# MJ808_clone_-_all_driver-_POC.net
KiCad netlist of a schematic drawn in EAGLE
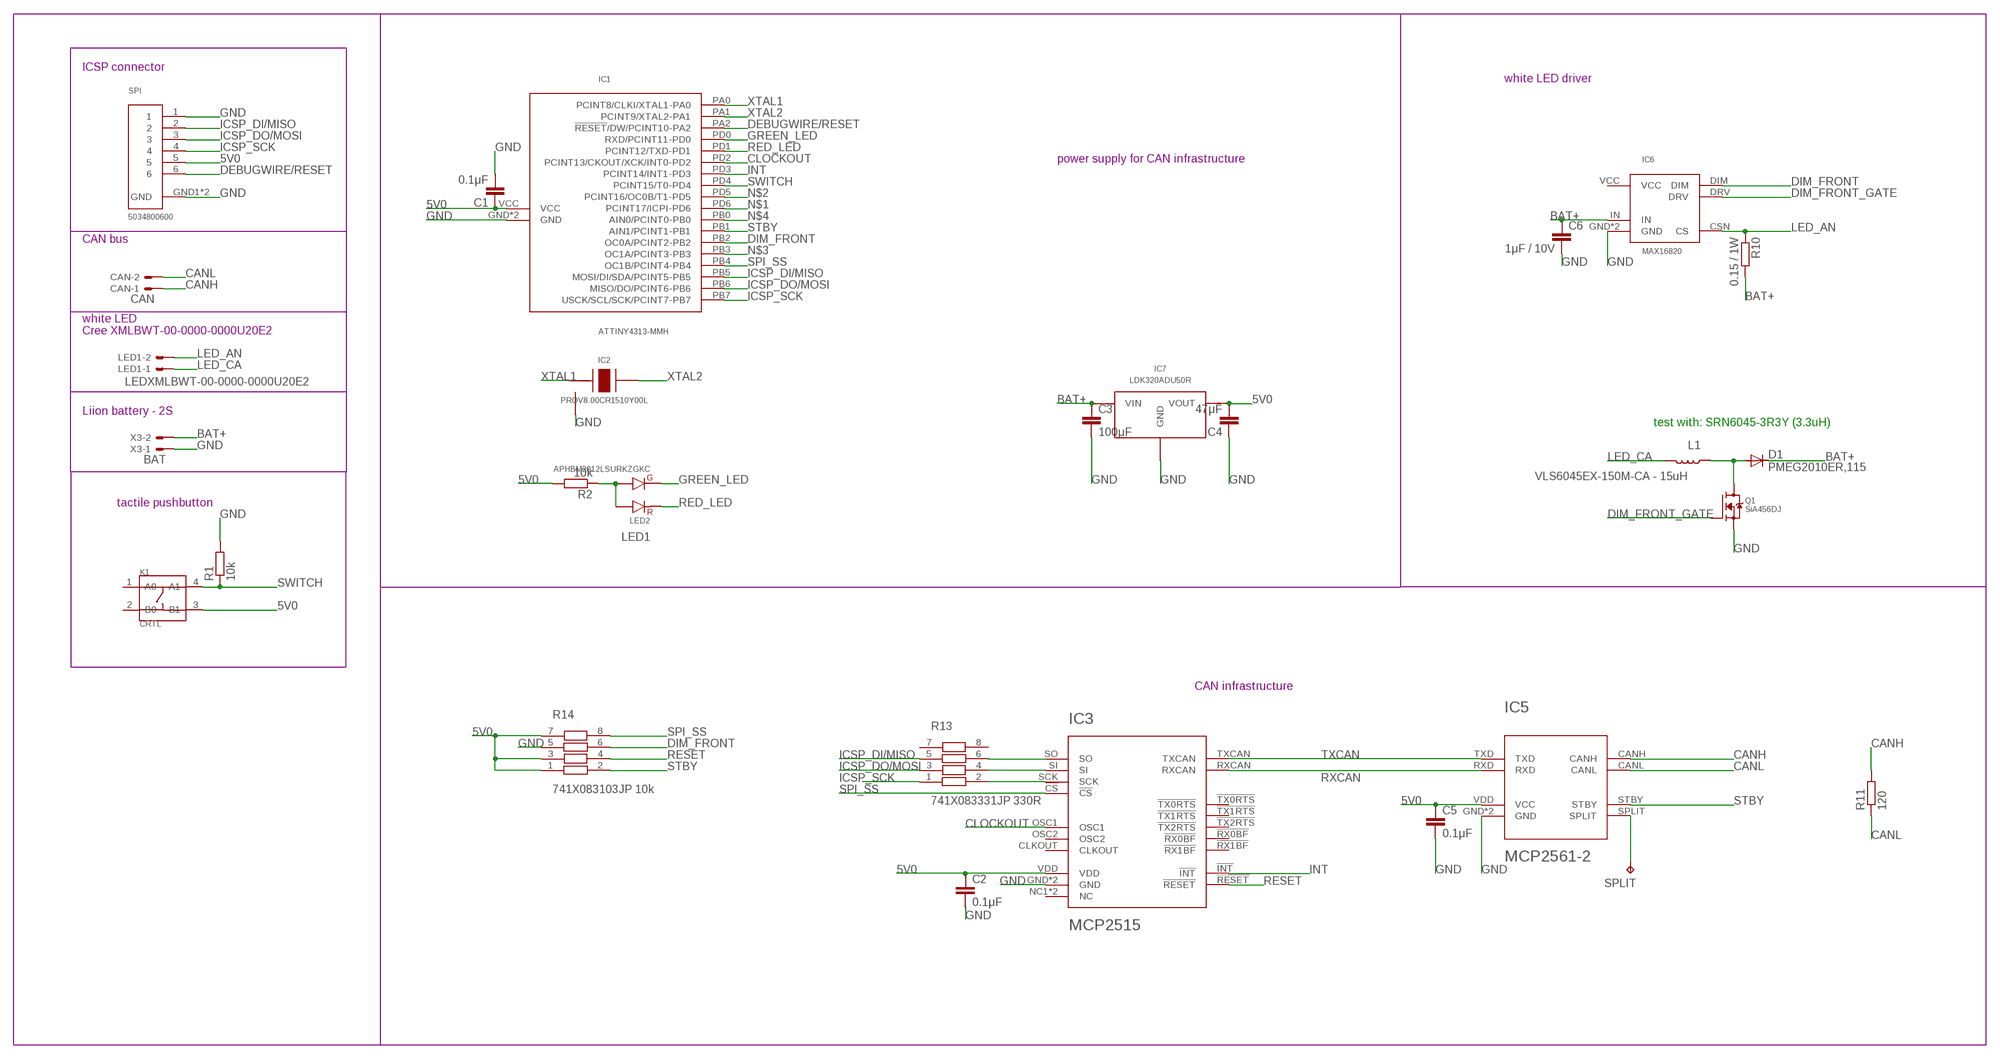
[diagram p0: schematic, sheet 1]

(export (version "E")
  (design (tool "Eeschema 10.0.6"))
  (components
    (comp (ref "C1")
      (value "0.1μF")
      (footprint "eagle-import:C0402")
      (libsource (lib "eagle-import") (part "C-EUC0402"))
    )
    (comp (ref "C2")
      (value "0.1μF")
      (footprint "eagle-import:C0402")
      (libsource (lib "eagle-import") (part "C-EUC0402"))
    )
    (comp (ref "C3")
      (value "100μF")
      (footprint "eagle-import:C1206")
      (libsource (lib "eagle-import") (part "C-EUC1206"))
    )
    (comp (ref "C4")
      (value "47μF")
      (footprint "eagle-import:C0805")
      (libsource (lib "eagle-import") (part "C-EUC0805"))
    )
    (comp (ref "C5")
      (value "0.1μF")
      (footprint "eagle-import:C0402")
      (libsource (lib "eagle-import") (part "C-EUC0402"))
    )
    (comp (ref "C6")
      (value "1μF / 10V")
      (footprint "eagle-import:C0805")
      (libsource (lib "eagle-import") (part "C-EUC0805"))
    )
    (comp (ref "CAN")
      (value "CAN")
      (footprint "eagle-import:22-23-2021")
      (fields (field (name "MF") "MOLEX") (field (name "MPN") "22-23-2021"))
      (libsource (lib "eagle-import") (part "22-23-2021"))
    )
    (comp (ref "D1")
      (value "PMEG2010ER,115")
      (footprint "eagle-import:SOD123")
      (libsource (lib "eagle-import") (part "DIODE-SOD123"))
    )
    (comp (ref "IC1")
      (value "ATTINY4313-MMH")
      (footprint "eagle-import:VQFN-20")
      (fields (field (name "SPICEPREFIX") "X"))
      (libsource (lib "eagle-import") (part "ATTINY4313VQFN-20"))
    )
    (comp (ref "IC2")
      (value "PRQV8.00CR1510Y00L")
      (footprint "eagle-import:SMT")
      (libsource (lib "eagle-import") (part "PRQV"))
    )
    (comp (ref "IC3")
      (value "MCP2515")
      (footprint "eagle-import:QFN20")
      (libsource (lib "eagle-import") (part "MCP2515-I-ML"))
    )
    (comp (ref "IC5")
      (value "MCP2561-2")
      (footprint "eagle-import:DFN10")
      (libsource (lib "eagle-import") (part "MCP2561-2"))
    )
    (comp (ref "IC6")
      (value "MAX16820")
      (footprint "eagle-import:TDFN-6-EP")
      (libsource (lib "eagle-import") (part "MAX16820"))
    )
    (comp (ref "IC7")
      (value "LDK320ADU50R")
      (footprint "eagle-import:SOT-89")
      (libsource (lib "eagle-import") (part "LDO"))
    )
    (comp (ref "K1")
      (value "CRTL")
      (footprint "eagle-import:SW4-SMD-6.0X6.0X5.0MM")
      (fields (field (name "MPN") "DTSM-62K-S-V-T/R(SN431)"))
      (libsource (lib "eagle-import") (part "SMD-SWITCH-TACTILE-SPST-NO(4P-D6.0MM)"))
    )
    (comp (ref "L1")
      (value "VLS6045EX-150M-CA - 15uH")
      (footprint "eagle-import:SRN6045")
      (libsource (lib "eagle-import") (part "INDUCTOR-SRN6045-33UH"))
    )
    (comp (ref "LED1")
      (value "LEDXMLBWT-00-0000-0000U20E2")
      (footprint "eagle-import:22-23-2021")
      (fields (field (name "MF") "MOLEX") (field (name "MPN") "22-23-2021"))
      (libsource (lib "eagle-import") (part "22-23-2021"))
    )
    (comp (ref "LED2")
      (value "APHBM2012LSURKZGKC")
      (footprint "eagle-import:SMD")
      (libsource (lib "eagle-import") (part "APHBM2012LSURKZGKC"))
    )
    (comp (ref "Q1")
      (value "SiA456DJ")
      (footprint "eagle-import:SC-70-6")
      (libsource (lib "eagle-import") (part "SIA456DJ"))
    )
    (comp (ref "R1")
      (value "10k")
      (footprint "eagle-import:R0402")
      (libsource (lib "eagle-import") (part "R-EU_R0402"))
    )
    (comp (ref "R2")
      (value "10k")
      (footprint "eagle-import:R0402")
      (libsource (lib "eagle-import") (part "R-EU_R0402"))
    )
    (comp (ref "R10")
      (value "0.15 / 1W")
      (footprint "eagle-import:R1210")
      (libsource (lib "eagle-import") (part "R-EU_R1210"))
    )
    (comp (ref "R11")
      (value "120")
      (footprint "eagle-import:R0805")
      (libsource (lib "eagle-import") (part "R-EU_R0805"))
    )
    (comp (ref "R13")
      (value "741X083331JP 330R")
      (footprint "eagle-import:0402")
      (libsource (lib "eagle-import") (part "741X083331JP"))
    )
    (comp (ref "R14")
      (value "741X083103JP 10k")
      (footprint "eagle-import:0402")
      (libsource (lib "eagle-import") (part "741X083331JP"))
    )
    (comp (ref "SPI")
      (value "5034800600")
      (footprint "eagle-import:SMT")
      (libsource (lib "eagle-import") (part "5034800600"))
    )
    (comp (ref "SPLIT")
      (value "TPB2,54")
      (footprint "eagle-import:B2,54")
      (libsource (lib "eagle-import") (part "TPB2,54"))
    )
    (comp (ref "X3")
      (value "BAT")
      (footprint "eagle-import:22-23-2021")
      (fields (field (name "MF") "MOLEX") (field (name "MPN") "22-23-2021"))
      (libsource (lib "eagle-import") (part "22-23-2021"))
    )
  )
  (nets
    (net (code "1") (name "/5V0") (class "Default")
      (node (ref "C1") (pin "1") (pinfunction "1_1") (pintype "passive"))
      (node (ref "C2") (pin "1") (pinfunction "1_1") (pintype "passive"))
      (node (ref "C4") (pin "2") (pinfunction "2_2") (pintype "passive"))
      (node (ref "C5") (pin "1") (pinfunction "1_1") (pintype "passive"))
      (node (ref "IC1") (pin "VCC") (pinfunction "VCC_VCC") (pintype "bidirectional"))
      (node (ref "IC3") (pin "VDD") (pinfunction "VDD_VDD") (pintype "power_in"))
      (node (ref "IC5") (pin "VDD") (pinfunction "VCC_VDD") (pintype "power_in"))
      (node (ref "IC7") (pin "VOUT") (pinfunction "VOUT_VOUT") (pintype "bidirectional"))
      (node (ref "K1") (pin "3") (pinfunction "B1_3") (pintype "bidirectional"))
      (node (ref "R14") (pin "1") (pinfunction "1_1") (pintype "bidirectional"))
      (node (ref "R14") (pin "3") (pinfunction "3_3") (pintype "bidirectional"))
      (node (ref "R14") (pin "7") (pinfunction "7_7") (pintype "bidirectional"))
      (node (ref "R2") (pin "2") (pinfunction "2_2") (pintype "passive"))
      (node (ref "SPI") (pin "5") (pinfunction "5_5") (pintype "bidirectional"))
    )
    (net (code "2") (name "/BAT+") (class "Default")
      (node (ref "C3") (pin "1") (pinfunction "1_1") (pintype "passive"))
      (node (ref "C6") (pin "1") (pinfunction "1_1") (pintype "passive"))
      (node (ref "D1") (pin "C") (pinfunction "C_C") (pintype "passive"))
      (node (ref "IC6") (pin "IN") (pinfunction "IN_IN") (pintype "power_in"))
      (node (ref "IC7") (pin "VIN") (pinfunction "VIN_VIN") (pintype "bidirectional"))
      (node (ref "R10") (pin "2") (pinfunction "2_2") (pintype "passive"))
      (node (ref "X3") (pin "2") (pinfunction "S_2") (pintype "passive"))
    )
    (net (code "3") (name "/CANH") (class "Default")
      (node (ref "CAN") (pin "1") (pinfunction "S_1") (pintype "passive"))
      (node (ref "IC5") (pin "CANH") (pinfunction "CANH_CANH") (pintype "bidirectional"))
      (node (ref "R11") (pin "2") (pinfunction "2_2") (pintype "passive"))
    )
    (net (code "4") (name "/CANL") (class "Default")
      (node (ref "CAN") (pin "2") (pinfunction "S_2") (pintype "passive"))
      (node (ref "IC5") (pin "CANL") (pinfunction "CANL_CANL") (pintype "bidirectional"))
      (node (ref "R11") (pin "1") (pinfunction "1_1") (pintype "passive"))
    )
    (net (code "5") (name "/CLOCKOUT") (class "Default")
      (node (ref "IC1") (pin "PD2") (pinfunction "PCINT13/CKOUT/XCK/INT0-PD2_PD2") (pintype "bidirectional"))
      (node (ref "IC3") (pin "OSC1") (pinfunction "OSC1_OSC1") (pintype "bidirectional"))
    )
    (net (code "6") (name "/DEBUGWIRE{slash}RESET") (class "Default")
      (node (ref "IC1") (pin "PA2") (pinfunction "~{RESET}/DW/PCINT10-PA2_PA2") (pintype "bidirectional"))
      (node (ref "SPI") (pin "6") (pinfunction "6_6") (pintype "bidirectional"))
    )
    (net (code "7") (name "/DIM_FRONT") (class "Default")
      (node (ref "IC1") (pin "PB2") (pinfunction "OC0A/PCINT2-PB2_PB2") (pintype "bidirectional"))
      (node (ref "IC6") (pin "DIM") (pinfunction "DIM_DIM") (pintype "bidirectional"))
      (node (ref "R14") (pin "6") (pinfunction "6_6") (pintype "bidirectional"))
    )
    (net (code "8") (name "/DIM_FRONT_GATE") (class "Default")
      (node (ref "IC6") (pin "DRV") (pinfunction "DRV_DRV") (pintype "bidirectional"))
      (node (ref "Q1") (pin "G") (pinfunction "G_G") (pintype "passive"))
    )
    (net (code "9") (name "/GND") (class "Default")
      (node (ref "C1") (pin "2") (pinfunction "2_2") (pintype "passive"))
      (node (ref "C2") (pin "2") (pinfunction "2_2") (pintype "passive"))
      (node (ref "C3") (pin "2") (pinfunction "2_2") (pintype "passive"))
      (node (ref "C4") (pin "1") (pinfunction "1_1") (pintype "passive"))
      (node (ref "C5") (pin "2") (pinfunction "2_2") (pintype "passive"))
      (node (ref "C6") (pin "2") (pinfunction "2_2") (pintype "passive"))
      (node (ref "IC1") (pin "GND") (pinfunction "GND_GND") (pintype "bidirectional"))
      (node (ref "IC1") (pin "GND1") (pinfunction "GND_GND1") (pintype "bidirectional"))
      (node (ref "IC2") (pin "GND") (pinfunction "GND_GND") (pintype "bidirectional"))
      (node (ref "IC3") (pin "GND") (pinfunction "GND_GND") (pintype "power_in"))
      (node (ref "IC3") (pin "GND6") (pinfunction "GND_GND6") (pintype "power_in"))
      (node (ref "IC5") (pin "GND") (pinfunction "GND_GND") (pintype "power_in"))
      (node (ref "IC5") (pin "VSS") (pinfunction "GND_VSS") (pintype "power_in"))
      (node (ref "IC6") (pin "GND") (pinfunction "GND_GND") (pintype "power_in"))
      (node (ref "IC6") (pin "GND1") (pinfunction "GND_GND1") (pintype "power_in"))
      (node (ref "IC7") (pin "GND") (pinfunction "GND_GND") (pintype "bidirectional"))
      (node (ref "Q1") (pin "S") (pinfunction "S_S") (pintype "passive"))
      (node (ref "R1") (pin "2") (pinfunction "2_2") (pintype "passive"))
      (node (ref "R14") (pin "5") (pinfunction "5_5") (pintype "bidirectional"))
      (node (ref "SPI") (pin "1") (pinfunction "1_1") (pintype "bidirectional"))
      (node (ref "SPI") (pin "GND1") (pinfunction "GND_GND1") (pintype "bidirectional"))
      (node (ref "SPI") (pin "GND2") (pinfunction "GND_GND2") (pintype "bidirectional"))
      (node (ref "X3") (pin "1") (pinfunction "S_1") (pintype "passive"))
    )
    (net (code "10") (name "/GREEN_LED") (class "Default")
      (node (ref "IC1") (pin "PD0") (pinfunction "RXD/PCINT11-PD0_PD0") (pintype "bidirectional"))
      (node (ref "LED2") (pin "3") (pinfunction "3_3") (pintype "bidirectional"))
    )
    (net (code "11") (name "/ICSP_DI{slash}MISO") (class "Default")
      (node (ref "IC1") (pin "PB5") (pinfunction "MOSI/DI/SDA/PCINT5-PB5_PB5") (pintype "bidirectional"))
      (node (ref "R13") (pin "5") (pinfunction "5_5") (pintype "bidirectional"))
      (node (ref "SPI") (pin "2") (pinfunction "2_2") (pintype "bidirectional"))
    )
    (net (code "12") (name "/ICSP_DO{slash}MOSI") (class "Default")
      (node (ref "IC1") (pin "PB6") (pinfunction "MISO/DO/PCINT6-PB6_PB6") (pintype "bidirectional"))
      (node (ref "R13") (pin "3") (pinfunction "3_3") (pintype "bidirectional"))
      (node (ref "SPI") (pin "3") (pinfunction "3_3") (pintype "bidirectional"))
    )
    (net (code "13") (name "/ICSP_SCK") (class "Default")
      (node (ref "IC1") (pin "PB7") (pinfunction "USCK/SCL/SCK/PCINT7-PB7_PB7") (pintype "bidirectional"))
      (node (ref "R13") (pin "1") (pinfunction "1_1") (pintype "bidirectional"))
      (node (ref "SPI") (pin "4") (pinfunction "4_4") (pintype "bidirectional"))
    )
    (net (code "14") (name "/INT") (class "Default")
      (node (ref "IC1") (pin "PD3") (pinfunction "PCINT14/INT1-PD3_PD3") (pintype "bidirectional"))
      (node (ref "IC3") (pin "!INT!") (pinfunction "~{INT}_!INT!") (pintype "bidirectional"))
    )
    (net (code "15") (name "/LED1") (class "Default")
      (node (ref "LED2") (pin "1") (pinfunction "1_1") (pintype "bidirectional"))
      (node (ref "LED2") (pin "4") (pinfunction "4_4") (pintype "bidirectional"))
      (node (ref "R2") (pin "1") (pinfunction "1_1") (pintype "passive"))
    )
    (net (code "16") (name "/LED_AN") (class "Default")
      (node (ref "IC6") (pin "CSN") (pinfunction "CS_CSN") (pintype "bidirectional"))
      (node (ref "LED1") (pin "2") (pinfunction "S_2") (pintype "passive"))
      (node (ref "R10") (pin "1") (pinfunction "1_1") (pintype "passive"))
    )
    (net (code "17") (name "/LED_CA") (class "Default")
      (node (ref "L1") (pin "2") (pinfunction "2_2") (pintype "passive"))
      (node (ref "LED1") (pin "1") (pinfunction "S_1") (pintype "passive"))
    )
    (net (code "18") (name "/N$1") (class "Default")
      (node (ref "IC1") (pin "PD6") (pinfunction "PCINT17/ICPI-PD6_PD6") (pintype "bidirectional"))
    )
    (net (code "19") (name "/N$2") (class "Default")
      (node (ref "IC1") (pin "PD5") (pinfunction "PCINT16/OC0B/T1-PD5_PD5") (pintype "bidirectional"))
    )
    (net (code "20") (name "/N$3") (class "Default")
      (node (ref "IC1") (pin "PB3") (pinfunction "OC1A/PCINT3-PB3_PB3") (pintype "bidirectional"))
    )
    (net (code "21") (name "/N$4") (class "Default")
      (node (ref "IC1") (pin "PB0") (pinfunction "AIN0/PCINT0-PB0_PB0") (pintype "bidirectional"))
    )
    (net (code "22") (name "/RED_LED") (class "Default")
      (node (ref "IC1") (pin "PD1") (pinfunction "PCINT12/TXD-PD1_PD1") (pintype "bidirectional"))
      (node (ref "LED2") (pin "2") (pinfunction "2_2") (pintype "bidirectional"))
    )
    (net (code "23") (name "/RESET") (class "Default")
      (node (ref "IC3") (pin "!RESET!") (pinfunction "~{RESET}_!RESET!") (pintype "bidirectional"))
      (node (ref "R14") (pin "4") (pinfunction "4_4") (pintype "bidirectional"))
    )
    (net (code "24") (name "/RXCAN") (class "Default")
      (node (ref "IC3") (pin "RXCAN") (pinfunction "RXCAN_RXCAN") (pintype "input"))
      (node (ref "IC5") (pin "RXD") (pinfunction "RXD_RXD") (pintype "output"))
    )
    (net (code "25") (name "/SPI_SS") (class "Default")
      (node (ref "IC1") (pin "PB4") (pinfunction "OC1B/PCINT4-PB4_PB4") (pintype "bidirectional"))
      (node (ref "IC3") (pin "!CS!") (pinfunction "~{CS}_!CS!") (pintype "bidirectional"))
      (node (ref "R14") (pin "8") (pinfunction "8_8") (pintype "bidirectional"))
    )
    (net (code "26") (name "/STBY") (class "Default")
      (node (ref "IC1") (pin "PB1") (pinfunction "AIN1/PCINT1-PB1_PB1") (pintype "bidirectional"))
      (node (ref "IC5") (pin "STBY") (pinfunction "STBY_STBY") (pintype "bidirectional"))
      (node (ref "R14") (pin "2") (pinfunction "2_2") (pintype "bidirectional"))
    )
    (net (code "27") (name "/SWITCH") (class "Default")
      (node (ref "IC1") (pin "PD4") (pinfunction "PCINT15/T0-PD4_PD4") (pintype "bidirectional"))
      (node (ref "K1") (pin "4") (pinfunction "A1_4") (pintype "bidirectional"))
      (node (ref "R1") (pin "1") (pinfunction "1_1") (pintype "passive"))
    )
    (net (code "28") (name "/TXCAN") (class "Default")
      (node (ref "IC3") (pin "TXCAN") (pinfunction "TXCAN_TXCAN") (pintype "output"))
      (node (ref "IC5") (pin "TXD") (pinfunction "TXD_TXD") (pintype "input"))
    )
    (net (code "29") (name "/VCC") (class "Default")
      (node (ref "IC6") (pin "VCC") (pinfunction "VCC_VCC") (pintype "power_in"))
    )
    (net (code "30") (name "/XTAL1") (class "Default")
      (node (ref "IC1") (pin "PA0") (pinfunction "PCINT8/CLKI/XTAL1-PA0_PA0") (pintype "bidirectional"))
      (node (ref "IC2") (pin "XTAL1") (pinfunction "XTAL1_XTAL1") (pintype "bidirectional"))
    )
    (net (code "31") (name "/XTAL2") (class "Default")
      (node (ref "IC1") (pin "PA1") (pinfunction "PCINT9/XTAL2-PA1_PA1") (pintype "bidirectional"))
      (node (ref "IC2") (pin "XTAL2") (pinfunction "XTAL2_XTAL2") (pintype "bidirectional"))
    )
    (net (code "32") (name "Net-(D1-PadA)") (class "Default")
      (node (ref "D1") (pin "A") (pinfunction "A_A") (pintype "passive"))
      (node (ref "L1") (pin "1") (pinfunction "1_1") (pintype "passive"))
      (node (ref "Q1") (pin "D") (pinfunction "D_D") (pintype "passive"))
    )
    (net (code "33") (name "Net-(IC3-PadSCK)") (class "Default")
      (node (ref "IC3") (pin "SCK") (pinfunction "SCK_SCK") (pintype "bidirectional"))
      (node (ref "R13") (pin "2") (pinfunction "2_2") (pintype "bidirectional"))
    )
    (net (code "34") (name "Net-(IC3-PadSI)") (class "Default")
      (node (ref "IC3") (pin "SI") (pinfunction "SI_SI") (pintype "input"))
      (node (ref "R13") (pin "4") (pinfunction "4_4") (pintype "bidirectional"))
    )
    (net (code "35") (name "Net-(IC3-PadSO)") (class "Default")
      (node (ref "IC3") (pin "SO") (pinfunction "SO_SO") (pintype "output"))
      (node (ref "R13") (pin "6") (pinfunction "6_6") (pintype "bidirectional"))
    )
    (net (code "36") (name "Net-(IC5-PadSPLIT)") (class "Default")
      (node (ref "IC5") (pin "SPLIT") (pinfunction "SPLIT_SPLIT") (pintype "bidirectional"))
      (node (ref "SPLIT") (pin "TP") (pinfunction "TP_TP") (pintype "input"))
    )
    (net (code "37") (name "unconnected-(IC3-NC-PadNC1)") (class "Default")
      (node (ref "IC3") (pin "NC1") (pinfunction "NC_NC1") (pintype "no_connect"))
    )
    (net (code "38") (name "unconnected-(IC3-NC-PadNC2)") (class "Default")
      (node (ref "IC3") (pin "NC2") (pinfunction "NC_NC2") (pintype "no_connect"))
    )
    (net (code "39") (name "unconnected-(IC3-PadCLKOUT)") (class "Default")
      (node (ref "IC3") (pin "CLKOUT") (pinfunction "CLKOUT_CLKOUT") (pintype "bidirectional"))
    )
    (net (code "40") (name "unconnected-(IC3-PadOSC2)") (class "Default")
      (node (ref "IC3") (pin "OSC2") (pinfunction "OSC2_OSC2") (pintype "bidirectional"))
    )
    (net (code "41") (name "unconnected-(IC3-~{RX0BF}-Pad!RX0BF!)") (class "Default")
      (node (ref "IC3") (pin "!RX0BF!") (pinfunction "~{RX0BF}_!RX0BF!") (pintype "bidirectional"))
    )
    (net (code "42") (name "unconnected-(IC3-~{RX1BF}-Pad!RX1BF!)") (class "Default")
      (node (ref "IC3") (pin "!RX1BF!") (pinfunction "~{RX1BF}_!RX1BF!") (pintype "bidirectional"))
    )
    (net (code "43") (name "unconnected-(IC3-~{TX0RTS}-Pad!TX0RTS!)") (class "Default")
      (node (ref "IC3") (pin "!TX0RTS!") (pinfunction "~{TX0RTS}_!TX0RTS!") (pintype "bidirectional"))
    )
    (net (code "44") (name "unconnected-(IC3-~{TX1RTS}-Pad!TX1RTS!)") (class "Default")
      (node (ref "IC3") (pin "!TX1RTS!") (pinfunction "~{TX1RTS}_!TX1RTS!") (pintype "bidirectional"))
    )
    (net (code "45") (name "unconnected-(IC3-~{TX2RTS}-Pad!TX2RTS!)") (class "Default")
      (node (ref "IC3") (pin "!TX2RTS!") (pinfunction "~{TX2RTS}_!TX2RTS!") (pintype "bidirectional"))
    )
    (net (code "46") (name "unconnected-(K1-A0-Pad1)") (class "Default")
      (node (ref "K1") (pin "1") (pinfunction "A0_1") (pintype "bidirectional"))
    )
    (net (code "47") (name "unconnected-(K1-B0-Pad2)") (class "Default")
      (node (ref "K1") (pin "2") (pinfunction "B0_2") (pintype "bidirectional"))
    )
    (net (code "48") (name "unconnected-(R13-Pad7)") (class "Default")
      (node (ref "R13") (pin "7") (pinfunction "7_7") (pintype "bidirectional"))
    )
    (net (code "49") (name "unconnected-(R13-Pad8)") (class "Default")
      (node (ref "R13") (pin "8") (pinfunction "8_8") (pintype "bidirectional"))
    )
  )
)
